# Sample_FPC_v1.net
KiCad netlist of a schematic drawn in Altium Designer
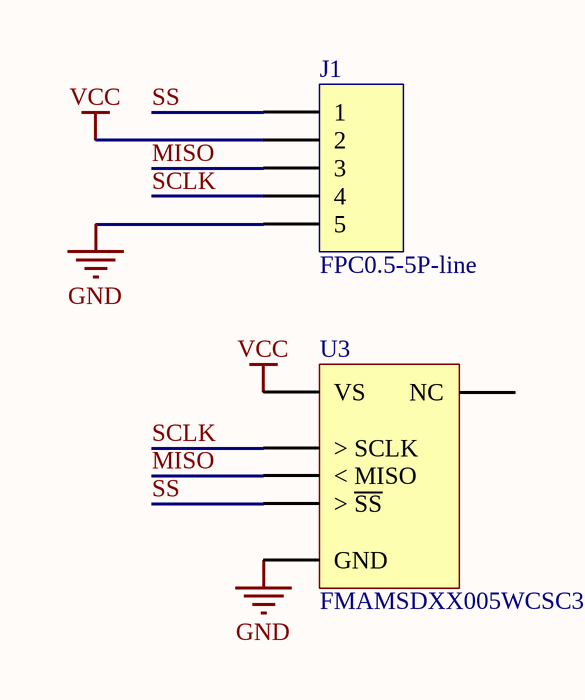
[diagram p0: Sample_FPC_v1.SchDoc]

(export (version "E")
  (design (tool "Eeschema 10.0.6"))
  (components
    (comp (ref "J1")
      (value "FPC0.5-5P-line")
      (footprint "FPC0.5-5P-Line")
      (libsource (lib "FMA_Sensor") (part "FPC0.5-5P-line"))
    )
    (comp (ref "U3")
      (value "FMAMSDXX005WCSC3")
      (footprint "FMA_MICROFORCE_6")
      (libsource (lib "FMA_Sensor") (part "FMAMSDXX005WCSC3"))
    )
  )
  (nets
    (net (code "1") (name "/MISO") (class "Default")
      (node (ref "J1") (pin "3") (pinfunction "3_3") (pintype "passive"))
      (node (ref "U3") (pin "5") (pinfunction "<_MISO_5") (pintype "passive"))
    )
    (net (code "2") (name "/SCLK") (class "Default")
      (node (ref "J1") (pin "4") (pinfunction "4_4") (pintype "passive"))
      (node (ref "U3") (pin "4") (pinfunction ">_SCLK_4") (pintype "passive"))
    )
    (net (code "3") (name "/SS") (class "Default")
      (node (ref "J1") (pin "1") (pinfunction "1_1") (pintype "passive"))
      (node (ref "U3") (pin "2") (pinfunction ">_~{SS}_2") (pintype "passive"))
    )
    (net (code "4") (name "GND") (class "Default")
      (node (ref "J1") (pin "5") (pinfunction "5_5") (pintype "passive"))
      (node (ref "U3") (pin "3") (pinfunction "GND_3") (pintype "passive"))
    )
    (net (code "5") (name "VCC") (class "Default")
      (node (ref "J1") (pin "2") (pinfunction "2_2") (pintype "passive"))
      (node (ref "U3") (pin "1") (pinfunction "VS_1") (pintype "passive"))
    )
    (net (code "6") (name "unconnected-(U3-NC-Pad6)") (class "Default")
      (node (ref "U3") (pin "6") (pinfunction "NC_6") (pintype "passive"))
    )
  )
)
